# cdc.net
KiCad netlist of a schematic drawn in EAGLE
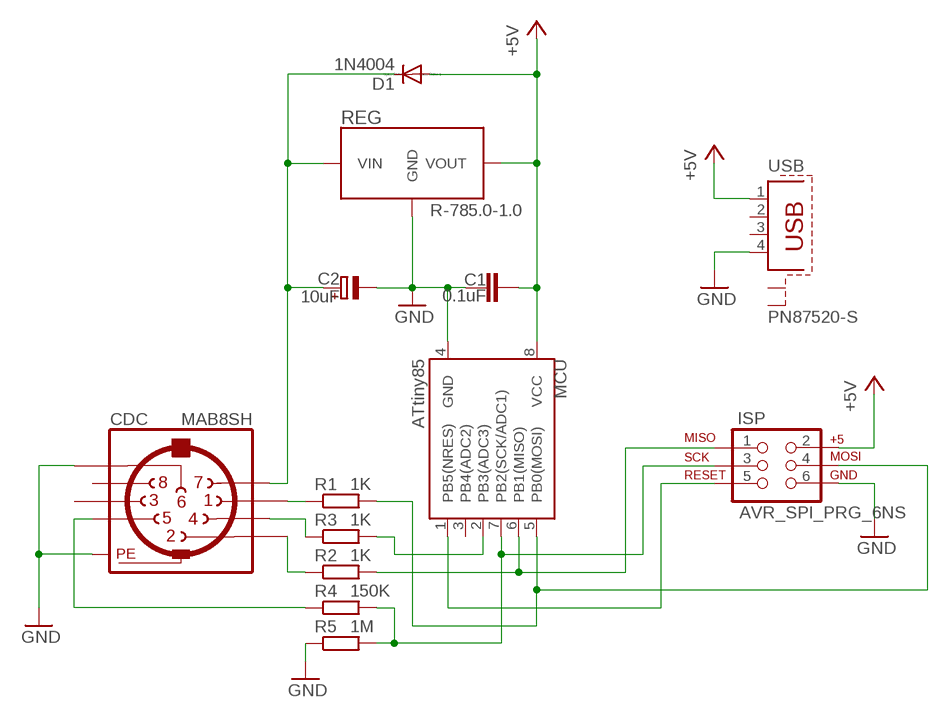
[diagram p0: schematic, sheet 1]

(export (version "E")
  (design (tool "Eeschema 10.0.6"))
  (components
    (comp (ref "C1")
      (value "0.1uF")
      (footprint "eagle-import:C5B3")
      (libsource (lib "eagle-import") (part "C5/3"))
    )
    (comp (ref "C2")
      (value "10uF")
      (footprint "eagle-import:E1,8-4")
      (libsource (lib "eagle-import") (part "CPOL-EUE1.8-4"))
    )
    (comp (ref "CDC")
      (value "MAB8SH")
      (footprint "eagle-import:MAB8SH")
      (fields (field (name "MF") "FARNELL") (field (name "MPN") "MAB 8 SH"))
      (libsource (lib "eagle-import") (part "MAB8SH"))
    )
    (comp (ref "D1")
      (value "1N4004")
      (footprint "eagle-import:DO41-10")
      (libsource (lib "eagle-import") (part "1N4004"))
    )
    (comp (ref "ISP")
      (value "AVR_SPI_PRG_6NS")
      (footprint "eagle-import:2X3-NS")
      (libsource (lib "eagle-import") (part "AVR_SPI_PRG_6NS"))
    )
    (comp (ref "MCU")
      (value "ATtiny85")
      (footprint "eagle-import:DIP08")
      (libsource (lib "eagle-import") (part "ATTINY45TINY45-20-DIP"))
    )
    (comp (ref "R1")
      (value "1K")
      (footprint "eagle-import:0207_7")
      (libsource (lib "eagle-import") (part "R-EU_0207/7"))
    )
    (comp (ref "R2")
      (value "1K")
      (footprint "eagle-import:0207_7")
      (libsource (lib "eagle-import") (part "R-EU_0207/7"))
    )
    (comp (ref "R3")
      (value "1K")
      (footprint "eagle-import:0207_7")
      (libsource (lib "eagle-import") (part "R-EU_0207/7"))
    )
    (comp (ref "R4")
      (value "150K")
      (footprint "eagle-import:0207_7")
      (libsource (lib "eagle-import") (part "R-EU_0207/7"))
    )
    (comp (ref "R5")
      (value "1M")
      (footprint "eagle-import:0207_7")
      (libsource (lib "eagle-import") (part "R-EU_0207/7"))
    )
    (comp (ref "REG")
      (value "VREG-RECOM-785.0-1.0")
      (footprint "eagle-import:VREG-RECOM-785.0-1.0")
      (libsource (lib "eagle-import") (part "VREG-RECOM-785.0-1.0"))
    )
    (comp (ref "USB")
      (value "PN87520-S")
      (footprint "eagle-import:PN87520-S")
      (libsource (lib "eagle-import") (part "PN87520-S"))
    )
  )
  (nets
    (net (code "1") (name "+5V") (class "Default")
      (node (ref "C1") (pin "2") (pinfunction "2_2") (pintype "passive"))
      (node (ref "D1") (pin "A") (pinfunction "A_A") (pintype "passive"))
      (node (ref "ISP") (pin "2") (pinfunction "2_2") (pintype "passive"))
      (node (ref "MCU") (pin "8") (pinfunction "VCC_8") (pintype "bidirectional"))
      (node (ref "REG") (pin "VOUT") (pinfunction "VOUT_VOUT") (pintype "bidirectional"))
      (node (ref "USB") (pin "1") (pinfunction "1_1") (pintype "passive"))
    )
    (net (code "2") (name "GND") (class "Default")
      (node (ref "C1") (pin "1") (pinfunction "1_1") (pintype "passive"))
      (node (ref "C2") (pin "-") (pinfunction "-_-") (pintype "passive"))
      (node (ref "CDC") (pin "6") (pinfunction "6_6") (pintype "passive"))
      (node (ref "CDC") (pin "PE") (pinfunction "PE_PE") (pintype "power_in"))
      (node (ref "CDC") (pin "PE@") (pinfunction "PE_PE@") (pintype "power_in"))
      (node (ref "ISP") (pin "6") (pinfunction "6_6") (pintype "passive"))
      (node (ref "MCU") (pin "4") (pinfunction "GND_4") (pintype "bidirectional"))
      (node (ref "R5") (pin "1") (pinfunction "1_1") (pintype "passive"))
      (node (ref "REG") (pin "GND") (pinfunction "GND_GND") (pintype "bidirectional"))
      (node (ref "USB") (pin "4") (pinfunction "4_4") (pintype "passive"))
    )
    (net (code "3") (name "Net-(C2-Pad+)") (class "Default")
      (node (ref "C2") (pin "+") (pinfunction "+_+") (pintype "passive"))
      (node (ref "CDC") (pin "7") (pinfunction "7_7") (pintype "passive"))
      (node (ref "D1") (pin "C") (pinfunction "C_C") (pintype "passive"))
      (node (ref "REG") (pin "VIN") (pinfunction "VIN_VIN") (pintype "bidirectional"))
    )
    (net (code "4") (name "Net-(CDC-Pad1)") (class "Default")
      (node (ref "CDC") (pin "1") (pinfunction "1_1") (pintype "passive"))
      (node (ref "R1") (pin "1") (pinfunction "1_1") (pintype "passive"))
    )
    (net (code "5") (name "Net-(CDC-Pad2)") (class "Default")
      (node (ref "CDC") (pin "2") (pinfunction "2_2") (pintype "passive"))
      (node (ref "R2") (pin "1") (pinfunction "1_1") (pintype "passive"))
    )
    (net (code "6") (name "Net-(CDC-Pad4)") (class "Default")
      (node (ref "CDC") (pin "4") (pinfunction "4_4") (pintype "passive"))
      (node (ref "R3") (pin "1") (pinfunction "1_1") (pintype "passive"))
    )
    (net (code "7") (name "Net-(CDC-Pad5)") (class "Default")
      (node (ref "CDC") (pin "5") (pinfunction "5_5") (pintype "passive"))
      (node (ref "R4") (pin "1") (pinfunction "1_1") (pintype "passive"))
    )
    (net (code "8") (name "Net-(MCU-PB0(MOSI))") (class "Default")
      (node (ref "ISP") (pin "4") (pinfunction "4_4") (pintype "passive"))
      (node (ref "MCU") (pin "5") (pinfunction "PB0(MOSI)_5") (pintype "bidirectional"))
      (node (ref "R1") (pin "2") (pinfunction "2_2") (pintype "passive"))
    )
    (net (code "9") (name "Net-(MCU-PB1(MISO))") (class "Default")
      (node (ref "ISP") (pin "1") (pinfunction "1_1") (pintype "passive"))
      (node (ref "MCU") (pin "6") (pinfunction "PB1(MISO)_6") (pintype "bidirectional"))
      (node (ref "R2") (pin "2") (pinfunction "2_2") (pintype "passive"))
    )
    (net (code "10") (name "Net-(MCU-PB2(SCK{slash}ADC1))") (class "Default")
      (node (ref "ISP") (pin "3") (pinfunction "3_3") (pintype "passive"))
      (node (ref "MCU") (pin "7") (pinfunction "PB2(SCK/ADC1)_7") (pintype "bidirectional"))
      (node (ref "R4") (pin "2") (pinfunction "2_2") (pintype "passive"))
      (node (ref "R5") (pin "2") (pinfunction "2_2") (pintype "passive"))
    )
    (net (code "11") (name "Net-(MCU-PB3(ADC3))") (class "Default")
      (node (ref "MCU") (pin "2") (pinfunction "PB3(ADC3)_2") (pintype "bidirectional"))
      (node (ref "R3") (pin "2") (pinfunction "2_2") (pintype "passive"))
    )
    (net (code "12") (name "Net-(MCU-PB5(NRES))") (class "Default")
      (node (ref "ISP") (pin "5") (pinfunction "5_5") (pintype "passive"))
      (node (ref "MCU") (pin "1") (pinfunction "PB5(NRES)_1") (pintype "bidirectional"))
    )
    (net (code "13") (name "unconnected-(CDC-Pad3)") (class "Default")
      (node (ref "CDC") (pin "3") (pinfunction "3_3") (pintype "passive"))
    )
    (net (code "14") (name "unconnected-(CDC-Pad8)") (class "Default")
      (node (ref "CDC") (pin "8") (pinfunction "8_8") (pintype "passive"))
    )
    (net (code "15") (name "unconnected-(MCU-PB4(ADC2)-Pad3)") (class "Default")
      (node (ref "MCU") (pin "3") (pinfunction "PB4(ADC2)_3") (pintype "bidirectional"))
    )
    (net (code "16") (name "unconnected-(USB-Pad2)") (class "Default")
      (node (ref "USB") (pin "2") (pinfunction "2_2") (pintype "passive"))
    )
    (net (code "17") (name "unconnected-(USB-Pad3)") (class "Default")
      (node (ref "USB") (pin "3") (pinfunction "3_3") (pintype "passive"))
    )
    (net (code "18") (name "unconnected-(USB-PadS1)") (class "Default")
      (node (ref "USB") (pin "S1") (pinfunction "S1_S1") (pintype "passive"))
    )
    (net (code "19") (name "unconnected-(USB-PadS2)") (class "Default")
      (node (ref "USB") (pin "S2") (pinfunction "S2_S2") (pintype "passive"))
    )
  )
)
